# ESP8266_GSM_switch.net
KiCad netlist of a schematic drawn in Altium Designer
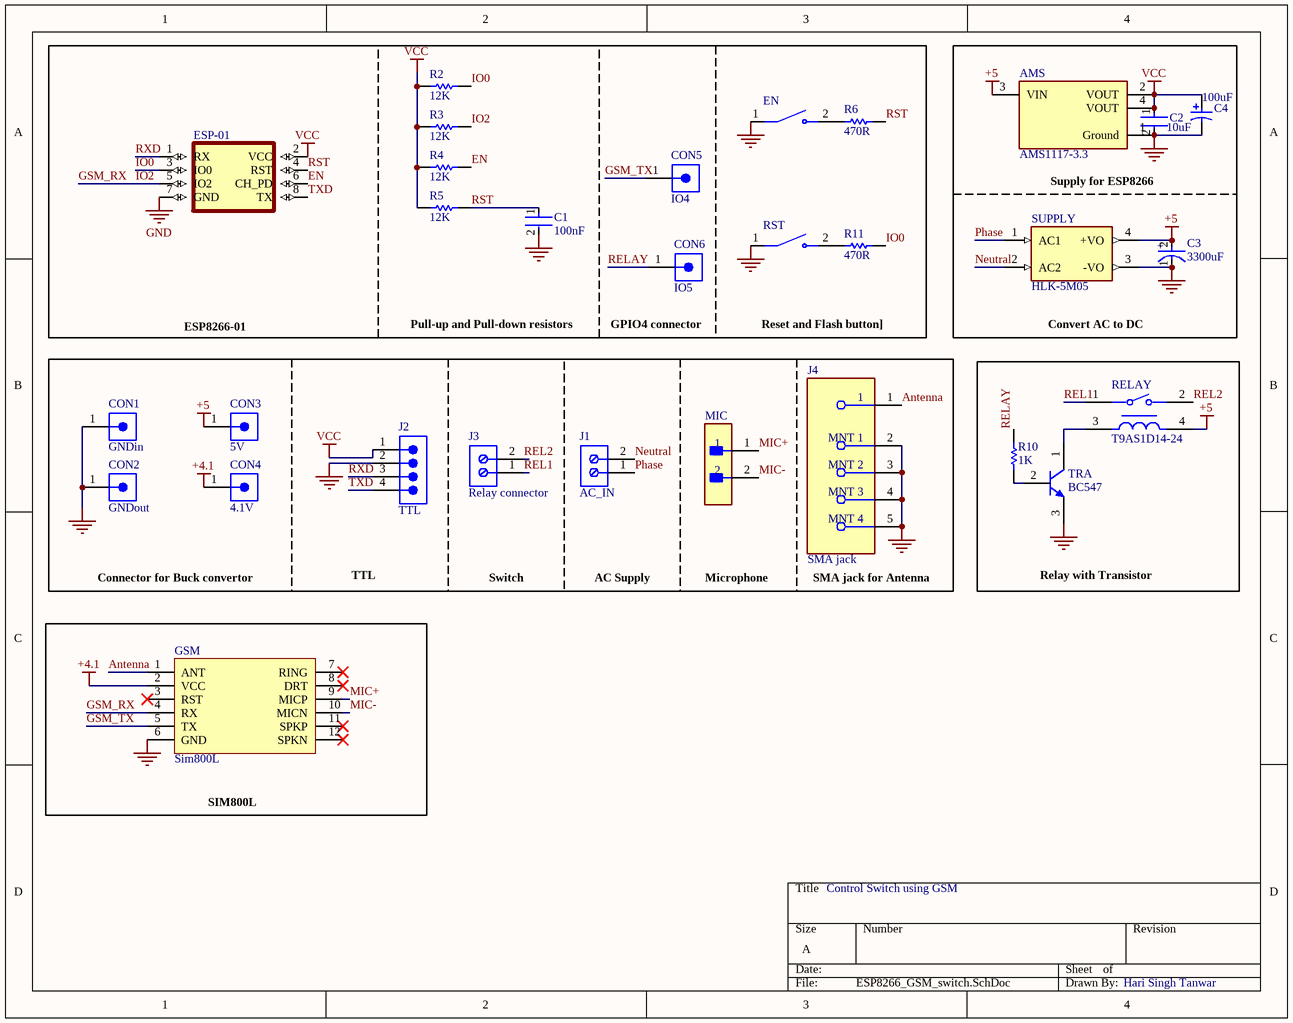
[diagram p0: ESP8266_GSM_switch.SchDoc]

(export (version "E")
  (design (tool "Eeschema 10.0.6"))
  (components
    (comp (ref "AMS")
      (value "AMS1117-3.3")
      (footprint "FP-AMS1117-IPC_C")
      (description "LDO Voltage Regulators 1A, 3.3V")
      (fields
        (field (name "OCTOPART") "https://octopart.com/ams1117-3.3-advanced+monolithic+systems-25899300")
        (field (name "MANUFACTURER") "Advanced Monolithic Systems")
      )
      (libsource (lib "Altium Content Vault") (part "8bdbb5f8e77002000e30dd2845d0354"))
    )
    (comp (ref "C1")
      (value "100nF")
      (footprint "FP-0805-L_2_01_0_2-W_1_25-IPC_B")
      (description "General Purpose Ceramic Capacitor, 0805, 100nF, 10%, X7R, 15%, 100V")
      (fields (field (name "VOLTAGE") "100V") (field (name "TOLERANCE") "10%"))
      (libsource (lib "Altium Content Vault") (part "b4654b650e69147ec39a6b967a45e02"))
    )
    (comp (ref "C2")
      (value "10uF")
      (footprint "FP-C0805C-DG-MFG")
      (description "CAP CER 10UF 10V X5R 0805")
      (fields (field (name "TOLERANCE") "10%") (field (name "MANUFACTURER PART NUMBER") "C0805C106K8PACTU"))
      (libsource (lib "Altium Content Vault") (part "11868f565c42a9108669ba33697ecf6"))
    )
    (comp (ref "C3")
      (value "3300uF")
      (footprint "FP-RAD-TH-D_12_5_0_5-L_40-MFG")
      (description "Aluminum Electrolytic Capacitors (Radial Lead Type) AEC-Q200 Qualified 3300uF ±20% 25V")
      (fields (field (name "TOLERANCE") "20%") (field (name "VOLTAGE") "25V"))
      (libsource (lib "Altium Content Vault") (part "203bc49f2ac43e59fd269a8c329ed05"))
    )
    (comp (ref "C4")
      (value "100uF")
      (footprint "PNSC-FK-V-D8_V")
      (fields (field (name "MANUFACTURER") "Panasonic"))
      (libsource (lib "Altium Content Vault") (part "CAP-P-2"))
    )
    (comp (ref "CON1")
      (value "GNDin")
      (footprint "61300111121")
      (libsource (lib "Altium Content Vault") (part "Header_Male_1R_01P"))
    )
    (comp (ref "CON2")
      (value "GNDout")
      (footprint "61300111121")
      (libsource (lib "Altium Content Vault") (part "Header_Male_1R_01P"))
    )
    (comp (ref "CON3")
      (value "5V")
      (footprint "61300111121")
      (libsource (lib "Altium Content Vault") (part "Header_Male_1R_01P"))
    )
    (comp (ref "CON4")
      (value "4.1V")
      (footprint "61300111121")
      (libsource (lib "Altium Content Vault") (part "Header_Male_1R_01P"))
    )
    (comp (ref "CON5")
      (value "IO4")
      (footprint "61300111121")
      (libsource (lib "Altium Content Vault") (part "Header_Male_1R_01P"))
    )
    (comp (ref "CON6")
      (value "IO5")
      (footprint "61300111121")
      (libsource (lib "Altium Content Vault") (part "Header_Male_1R_01P"))
    )
    (comp (ref "EN")
      (value "TS09-63-25-WT-160-SMT-TR")
      (footprint "SW_TS09-63-25-WT-160-SMT-TR")
      (libsource (lib "TS09-63-25-WT-160-SMT-TR") (part "TS09-63-25-WT-160-SMT-TR"))
    )
    (comp (ref "ESP-01")
      (value "ESP-01")
      (footprint "ESP-01")
      (description "ESP8266 ESP-01 Transceiver; 802.11 b/g/n (Wi-Fi, WiFi, WLAN) Evaluation Board")
      (fields (field (name "MF") "AI-Thinker"))
      (libsource (lib "ESP-01") (part "ESP-01"))
    )
    (comp (ref "GSM")
      (value "Sim800L")
      (footprint "Sim800L")
      (libsource (lib "Sim800L_Module") (part "Sim800L"))
    )
    (comp (ref "J1")
      (value "AC_IN")
      (footprint "691137710002")
      (libsource (lib "Altium Content Vault") (part "TBL - 1R - 02P - Screw"))
    )
    (comp (ref "J2")
      (value "TTL")
      (footprint "61300411121")
      (libsource (lib "Altium Content Vault") (part "Header_Male_1R_04P"))
    )
    (comp (ref "J3")
      (value "Relay connector")
      (footprint "691137710002")
      (libsource (lib "Altium Content Vault") (part "TBL - 1R - 02P - Screw"))
    )
    (comp (ref "J4")
      (value "SMA jack")
      (footprint "FP-221790-1-MFG")
      (description "CONN SMA JACK R/A 50 OHM PCB")
      (fields
        (field (name "OCTOPART") "https://octopart.com/2217901-te+connectivity+%2F+amp-3339836")
        (field (name "MANUFACTURER PART NUMBER") "221790-1")
      )
      (libsource (lib "Altium Content Vault") (part "c65b8a639cdaef1819ea20b5466f8fa"))
    )
    (comp (ref "MIC")
      (value "Microphone connector")
      (footprint "FP-B2B-XH-A_LF_SN-MFG")
      (description "CONN HEADER VERT 2POS 2.5MM")
      (libsource (lib "Altium Content Vault") (part "3bc925449376181038e59eaffc5286c"))
    )
    (comp (ref "R2")
      (value "12K")
      (footprint "RESC2013X70X40ML20T20")
      (fields (field (name "MANUFACTURER") "Panasonic") (field (name "PART NUMBER") "ERJ6ENF1202V"))
      (libsource (lib "Altium Content Vault") (part "RES"))
    )
    (comp (ref "R3")
      (value "12K")
      (footprint "RESC2013X70X40ML20T20")
      (fields (field (name "MANUFACTURER") "Panasonic") (field (name "PART NUMBER") "ERJ6ENF1202V"))
      (libsource (lib "Altium Content Vault") (part "RES"))
    )
    (comp (ref "R4")
      (value "12K")
      (footprint "RESC2013X70X40ML20T20")
      (fields (field (name "MANUFACTURER") "Panasonic") (field (name "PART NUMBER") "ERJ6ENF1202V"))
      (libsource (lib "Altium Content Vault") (part "RES"))
    )
    (comp (ref "R5")
      (value "12K")
      (footprint "RESC2013X70X40ML20T20")
      (fields (field (name "MANUFACTURER") "Panasonic") (field (name "PART NUMBER") "ERJ6ENF1202V"))
      (libsource (lib "Altium Content Vault") (part "RES"))
    )
    (comp (ref "R6")
      (value "470R")
      (footprint "RESC2013X70X40ML20T20")
      (description "Chip Resistor, 470 Ohm, +/- 1%, 0.125 W, -55 to 155 degC, 0805 (2012 Metric), RoHS, Tape and Reel")
      (fields (field (name "MANUFACTURER") "Panasonic"))
      (libsource (lib "Altium Content Vault") (part "RES-2"))
    )
    (comp (ref "R10")
      (value "1K")
      (footprint "RESC2013X60X40ML20T25")
      (fields (field (name "PART NUMBER") "ERA6AEB123V") (field (name "MANUFACTURER") "Panasonic"))
      (libsource (lib "Altium Content Vault") (part "RES"))
    )
    (comp (ref "R11")
      (value "470R")
      (footprint "RESC2013X70X40ML20T20")
      (description "Chip Resistor, 470 Ohm, +/- 1%, 0.125 W, -55 to 155 degC, 0805 (2012 Metric), RoHS, Tape and Reel")
      (fields (field (name "MANUFACTURER") "Panasonic"))
      (libsource (lib "Altium Content Vault") (part "RES-2"))
    )
    (comp (ref "RELAY")
      (value "T9AS1D14-24")
      (footprint "FP-T9AS1D14-24-MFG")
      (description "RELAY GEN PURPOSE SPST 30A 24V")
      (libsource (lib "Altium Content Vault") (part "df7b9bdefa3caac6631df0901911d96"))
    )
    (comp (ref "RST")
      (value "TS09-63-25-WT-160-SMT-TR")
      (footprint "SW_TS09-63-25-WT-160-SMT-TR")
      (libsource (lib "TS09-63-25-WT-160-SMT-TR") (part "TS09-63-25-WT-160-SMT-TR"))
    )
    (comp (ref "SUPPLY")
      (value "HLK-5M05")
      (footprint "CONV_HLK-5M05")
      (description "AC DC 220V to 5V 5W 5Watt Isolated Switching Step-Down Power Supply Module Converter")
      (fields (field (name "MF") "Hi-link"))
      (libsource (lib "HLK-5M05") (part "HLK-5M05"))
    )
    (comp (ref "TRA")
      (value "BC547")
      (footprint "ONSC-TO-92-3-29-11_AM_BL")
      (description "Amplifier Transistor, NPN Silicon, 3-Pin TO-92, Pb-Free, Tape and Reel")
      (fields (field (name "MANUFACTURER") "On Semiconductor") (field (name "PARTNUMBER") "BC547BRL1G"))
      (libsource (lib "Altium Content Vault") (part "ONSC-NPN-C1B2E3-3"))
    )
  )
  (nets
    (net (code "1") (name "+4.1") (class "Default")
      (node (ref "CON4") (pin "1") (pinfunction "1_1") (pintype "passive"))
      (node (ref "GSM") (pin "2") (pinfunction "VCC_2") (pintype "passive"))
    )
    (net (code "2") (name "+5") (class "Default")
      (node (ref "AMS") (pin "3") (pinfunction "VIN_3") (pintype "power_in"))
      (node (ref "C3") (pin "2") (pinfunction "A_2") (pintype "passive"))
      (node (ref "CON3") (pin "1") (pinfunction "1_1") (pintype "passive"))
      (node (ref "RELAY") (pin "4") (pinfunction "4_4") (pintype "passive"))
      (node (ref "SUPPLY") (pin "4") (pinfunction "+VO_4") (pintype "output"))
    )
    (net (code "3") (name "/Antenna") (class "Default")
      (node (ref "GSM") (pin "1") (pinfunction "ANT_1") (pintype "passive"))
      (node (ref "J4") (pin "1") (pinfunction "1_1") (pintype "passive"))
    )
    (net (code "4") (name "/EN") (class "Default")
      (node (ref "ESP-01") (pin "6") (pinfunction "CH_PD_6") (pintype "bidirectional"))
      (node (ref "R4") (pin "2") (pinfunction "2_2") (pintype "passive"))
    )
    (net (code "5") (name "/GSM_RX") (class "Default")
      (node (ref "ESP-01") (pin "5") (pinfunction "IO2_5") (pintype "bidirectional"))
      (node (ref "GSM") (pin "4") (pinfunction "RX_4") (pintype "passive"))
      (node (ref "R3") (pin "2") (pinfunction "2_2") (pintype "passive"))
    )
    (net (code "6") (name "/GSM_TX") (class "Default")
      (node (ref "CON5") (pin "1") (pinfunction "1_1") (pintype "passive"))
      (node (ref "GSM") (pin "5") (pinfunction "TX_5") (pintype "passive"))
    )
    (net (code "7") (name "/IO0") (class "Default")
      (node (ref "ESP-01") (pin "3") (pinfunction "IO0_3") (pintype "bidirectional"))
      (node (ref "R11") (pin "2") (pinfunction "2_2") (pintype "passive"))
      (node (ref "R2") (pin "2") (pinfunction "2_2") (pintype "passive"))
    )
    (net (code "8") (name "/MIC+") (class "Default")
      (node (ref "GSM") (pin "9") (pinfunction "MICP_9") (pintype "passive"))
      (node (ref "MIC") (pin "1") (pinfunction "1_1") (pintype "passive"))
    )
    (net (code "9") (name "/MIC-") (class "Default")
      (node (ref "GSM") (pin "10") (pinfunction "MICN_10") (pintype "passive"))
      (node (ref "MIC") (pin "2") (pinfunction "2_2") (pintype "passive"))
    )
    (net (code "10") (name "/Neutral") (class "Default")
      (node (ref "J1") (pin "2") (pinfunction "2_2") (pintype "passive"))
      (node (ref "SUPPLY") (pin "2") (pinfunction "AC2_2") (pintype "input"))
    )
    (net (code "11") (name "/Phase") (class "Default")
      (node (ref "J1") (pin "1") (pinfunction "1_1") (pintype "passive"))
      (node (ref "SUPPLY") (pin "1") (pinfunction "AC1_1") (pintype "input"))
    )
    (net (code "12") (name "/REL1") (class "Default")
      (node (ref "J3") (pin "1") (pinfunction "1_1") (pintype "passive"))
      (node (ref "RELAY") (pin "1") (pinfunction "1_1") (pintype "passive"))
    )
    (net (code "13") (name "/REL2") (class "Default")
      (node (ref "J3") (pin "2") (pinfunction "2_2") (pintype "passive"))
      (node (ref "RELAY") (pin "2") (pinfunction "2_2") (pintype "passive"))
    )
    (net (code "14") (name "/RELAY") (class "Default")
      (node (ref "CON6") (pin "1") (pinfunction "1_1") (pintype "passive"))
      (node (ref "R10") (pin "2") (pinfunction "2_2") (pintype "passive"))
    )
    (net (code "15") (name "/RST") (class "Default")
      (node (ref "C1") (pin "1") (pinfunction "1_1") (pintype "passive"))
      (node (ref "ESP-01") (pin "4") (pinfunction "RST_4") (pintype "bidirectional"))
      (node (ref "R5") (pin "2") (pinfunction "2_2") (pintype "passive"))
      (node (ref "R6") (pin "2") (pinfunction "2_2") (pintype "passive"))
    )
    (net (code "16") (name "/RXD") (class "Default")
      (node (ref "ESP-01") (pin "1") (pinfunction "RX_1") (pintype "bidirectional"))
      (node (ref "J2") (pin "3") (pinfunction "3_3") (pintype "passive"))
    )
    (net (code "17") (name "/TXD") (class "Default")
      (node (ref "ESP-01") (pin "8") (pinfunction "TX_8") (pintype "bidirectional"))
      (node (ref "J2") (pin "4") (pinfunction "4_4") (pintype "passive"))
    )
    (net (code "18") (name "GND") (class "Default")
      (node (ref "AMS") (pin "1") (pinfunction "Ground_1") (pintype "power_in"))
      (node (ref "C1") (pin "2") (pinfunction "2_2") (pintype "passive"))
      (node (ref "C2") (pin "2") (pinfunction "2_2") (pintype "passive"))
      (node (ref "C3") (pin "1") (pinfunction "C_1") (pintype "passive"))
      (node (ref "C4") (pin "2") (pinfunction "2_2") (pintype "passive"))
      (node (ref "CON1") (pin "1") (pinfunction "1_1") (pintype "passive"))
      (node (ref "CON2") (pin "1") (pinfunction "1_1") (pintype "passive"))
      (node (ref "EN") (pin "1") (pinfunction "1_1") (pintype "passive"))
      (node (ref "ESP-01") (pin "7") (pinfunction "GND_7") (pintype "bidirectional"))
      (node (ref "GSM") (pin "6") (pinfunction "GND_6") (pintype "passive"))
      (node (ref "J2") (pin "2") (pinfunction "2_2") (pintype "passive"))
      (node (ref "J4") (pin "2") (pinfunction "MNT_1_2") (pintype "passive"))
      (node (ref "J4") (pin "3") (pinfunction "MNT_2_3") (pintype "passive"))
      (node (ref "J4") (pin "4") (pinfunction "MNT_3_4") (pintype "passive"))
      (node (ref "J4") (pin "5") (pinfunction "MNT_4_5") (pintype "passive"))
      (node (ref "RST") (pin "1") (pinfunction "1_1") (pintype "passive"))
      (node (ref "SUPPLY") (pin "3") (pinfunction "-VO_3") (pintype "output"))
      (node (ref "TRA") (pin "3") (pinfunction "E_3") (pintype "passive"))
    )
    (net (code "19") (name "Net-(EN-Pad2)") (class "Default")
      (node (ref "EN") (pin "2") (pinfunction "2_2") (pintype "passive"))
      (node (ref "R6") (pin "1") (pinfunction "1_1") (pintype "passive"))
    )
    (net (code "20") (name "Net-(R11-Pad1)") (class "Default")
      (node (ref "R11") (pin "1") (pinfunction "1_1") (pintype "passive"))
      (node (ref "RST") (pin "2") (pinfunction "2_2") (pintype "passive"))
    )
    (net (code "21") (name "Net-(TRA-B)") (class "Default")
      (node (ref "R10") (pin "1") (pinfunction "1_1") (pintype "passive"))
      (node (ref "TRA") (pin "2") (pinfunction "B_2") (pintype "passive"))
    )
    (net (code "22") (name "Net-(TRA-C)") (class "Default")
      (node (ref "RELAY") (pin "3") (pinfunction "3_3") (pintype "passive"))
      (node (ref "TRA") (pin "1") (pinfunction "C_1") (pintype "passive"))
    )
    (net (code "23") (name "VCC") (class "Default")
      (node (ref "AMS") (pin "2") (pinfunction "VOUT_2") (pintype "passive"))
      (node (ref "AMS") (pin "4") (pinfunction "VOUT_4") (pintype "passive"))
      (node (ref "C2") (pin "1") (pinfunction "1_1") (pintype "passive"))
      (node (ref "C4") (pin "1") (pinfunction "1_1") (pintype "passive"))
      (node (ref "ESP-01") (pin "2") (pinfunction "VCC_2") (pintype "bidirectional"))
      (node (ref "J2") (pin "1") (pinfunction "1_1") (pintype "passive"))
      (node (ref "R2") (pin "1") (pinfunction "1_1") (pintype "passive"))
      (node (ref "R3") (pin "1") (pinfunction "1_1") (pintype "passive"))
      (node (ref "R4") (pin "1") (pinfunction "1_1") (pintype "passive"))
      (node (ref "R5") (pin "1") (pinfunction "1_1") (pintype "passive"))
    )
    (net (code "24") (name "unconnected-(GSM-DRT-Pad8)") (class "Default")
      (node (ref "GSM") (pin "8") (pinfunction "DRT_8") (pintype "passive+no_connect"))
    )
    (net (code "25") (name "unconnected-(GSM-RING-Pad7)") (class "Default")
      (node (ref "GSM") (pin "7") (pinfunction "RING_7") (pintype "passive+no_connect"))
    )
    (net (code "26") (name "unconnected-(GSM-RST-Pad3)") (class "Default")
      (node (ref "GSM") (pin "3") (pinfunction "RST_3") (pintype "passive+no_connect"))
    )
    (net (code "27") (name "unconnected-(GSM-SPKN-Pad12)") (class "Default")
      (node (ref "GSM") (pin "12") (pinfunction "SPKN_12") (pintype "passive+no_connect"))
    )
    (net (code "28") (name "unconnected-(GSM-SPKP-Pad11)") (class "Default")
      (node (ref "GSM") (pin "11") (pinfunction "SPKP_11") (pintype "passive+no_connect"))
    )
  )
)
